# kegboard_rpt.net
KiCad netlist of a schematic drawn in EAGLE
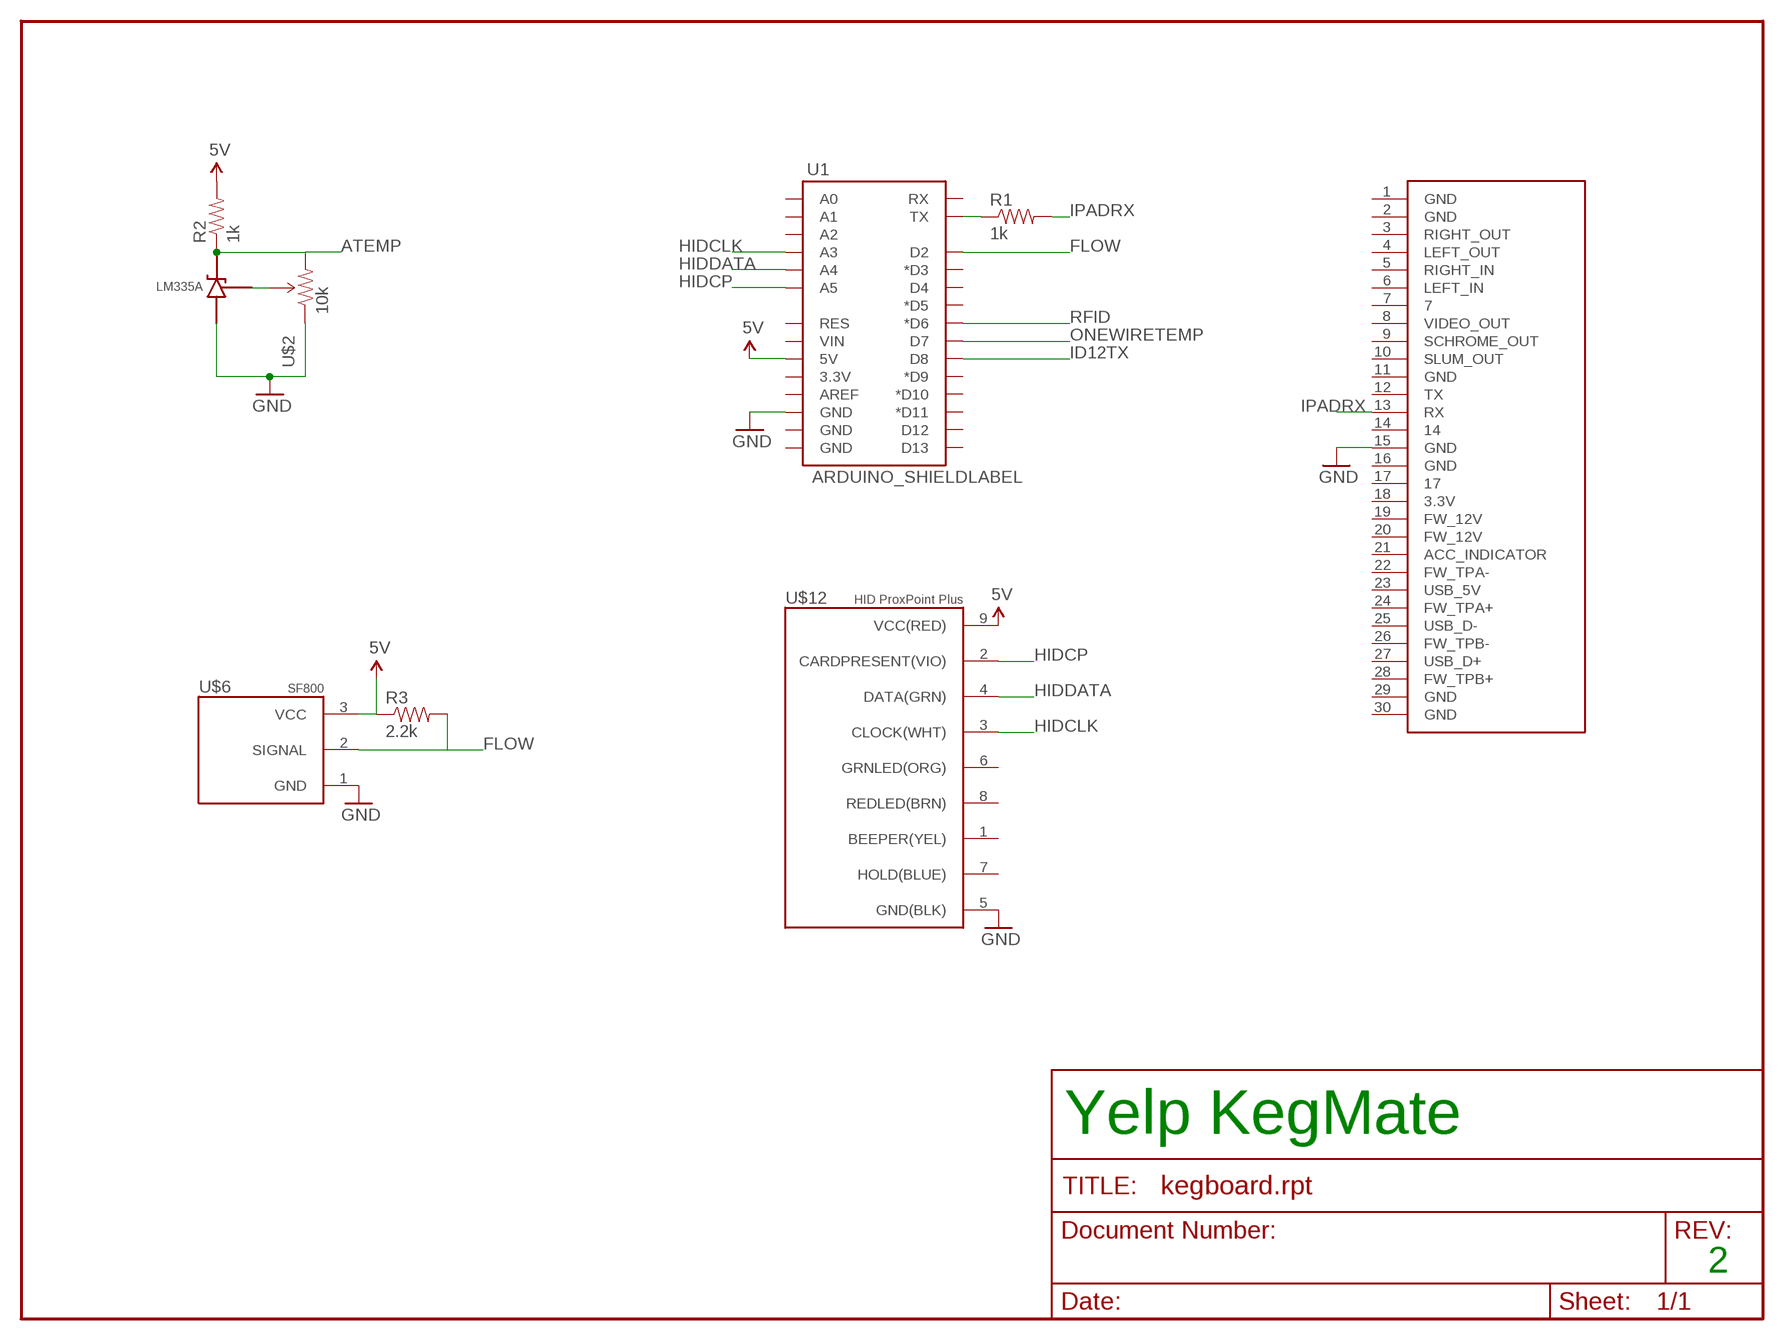
[diagram p0: schematic, sheet 1]

(export (version "E")
  (design (tool "Eeschema 10.0.6"))
  (components
    (comp (ref "R1")
      (value "1k")
      (footprint "eagle-import:AXIAL-0.3")
      (libsource (lib "eagle-import") (part "RESISTORPTH1"))
    )
    (comp (ref "R2")
      (value "1k")
      (footprint "eagle-import:AXIAL-0.3")
      (libsource (lib "eagle-import") (part "RESISTORPTH1"))
    )
    (comp (ref "R3")
      (value "2.2k")
      (footprint "eagle-import:AXIAL-0.3")
      (libsource (lib "eagle-import") (part "RESISTORPTH1"))
    )
    (comp (ref "U$1")
      (value "IPOD_CONNECTOR_MALE")
      (footprint "eagle-import:IPOD_MALE_CONNECTOR")
      (libsource (lib "eagle-import") (part "IPOD_CONNECTOR_MALE"))
    )
    (comp (ref "U$2")
      (value "10k")
      (footprint "eagle-import:3362U-2")
      (libsource (lib "eagle-import") (part "TRIMPOT"))
    )
    (comp (ref "U$6")
      (value "SF800")
      (footprint "eagle-import:1X03")
      (libsource (lib "eagle-import") (part "SF800"))
    )
    (comp (ref "U$11")
      (value "LM335A")
      (footprint "eagle-import:TO-92")
      (libsource (lib "eagle-import") (part "LM335A"))
    )
    (comp (ref "U$12")
      (value "HIDPROXPOINT")
      (footprint "eagle-import:2X5")
      (libsource (lib "eagle-import") (part "HIDPROXPOINT"))
    )
    (comp (ref "U1")
      (value "ARDUINO_SHIELDLABEL")
      (footprint "eagle-import:DUEMILANOVE_SHIELD")
      (libsource (lib "eagle-import") (part "ARDUINO_SHIELDLABEL"))
    )
  )
  (nets
    (net (code "1") (name "/ATEMP") (class "Default")
      (node (ref "R2") (pin "P$1") (pinfunction "1_P$1") (pintype "passive"))
      (node (ref "U$11") (pin "C1") (pinfunction "+_C1") (pintype "bidirectional"))
      (node (ref "U$2") (pin "3") (pinfunction "CW_3") (pintype "passive"))
    )
    (net (code "2") (name "/FLOW") (class "Default")
      (node (ref "R3") (pin "P$2") (pinfunction "2_P$2") (pintype "passive"))
      (node (ref "U$6") (pin "2") (pinfunction "SIGNAL_2") (pintype "bidirectional"))
      (node (ref "U1") (pin "D2") (pinfunction "D2_D2") (pintype "bidirectional"))
    )
    (net (code "3") (name "/HIDCLK") (class "Default")
      (node (ref "U$12") (pin "3") (pinfunction "CLOCK(WHT)_3") (pintype "bidirectional"))
      (node (ref "U1") (pin "A3") (pinfunction "A3_A3") (pintype "bidirectional"))
    )
    (net (code "4") (name "/HIDCP") (class "Default")
      (node (ref "U$12") (pin "2") (pinfunction "CARDPRESENT(VIO)_2") (pintype "bidirectional"))
      (node (ref "U1") (pin "A5") (pinfunction "A5_A5") (pintype "bidirectional"))
    )
    (net (code "5") (name "/HIDDATA") (class "Default")
      (node (ref "U$12") (pin "4") (pinfunction "DATA(GRN)_4") (pintype "bidirectional"))
      (node (ref "U1") (pin "A4") (pinfunction "A4_A4") (pintype "bidirectional"))
    )
    (net (code "6") (name "/ID12TX") (class "Default")
      (node (ref "U1") (pin "D8") (pinfunction "D8_D8") (pintype "bidirectional"))
    )
    (net (code "7") (name "/IPADRX") (class "Default")
      (node (ref "R1") (pin "P$2") (pinfunction "2_P$2") (pintype "passive"))
      (node (ref "U$1") (pin "13") (pinfunction "RX_13") (pintype "bidirectional"))
    )
    (net (code "8") (name "/ONEWIRETEMP") (class "Default")
      (node (ref "U1") (pin "D7") (pinfunction "D7_D7") (pintype "bidirectional"))
    )
    (net (code "9") (name "/RFID") (class "Default")
      (node (ref "U1") (pin "D6") (pinfunction "*D6_D6") (pintype "bidirectional"))
    )
    (net (code "10") (name "5V") (class "Default")
      (node (ref "R2") (pin "P$2") (pinfunction "2_P$2") (pintype "passive"))
      (node (ref "R3") (pin "P$1") (pinfunction "1_P$1") (pintype "passive"))
      (node (ref "U$12") (pin "9") (pinfunction "VCC(RED)_9") (pintype "bidirectional"))
      (node (ref "U$6") (pin "3") (pinfunction "VCC_3") (pintype "bidirectional"))
      (node (ref "U1") (pin "5V") (pinfunction "5V_5V") (pintype "bidirectional"))
    )
    (net (code "11") (name "GND") (class "Default")
      (node (ref "U$1") (pin "15") (pinfunction "GND_15") (pintype "bidirectional"))
      (node (ref "U$11") (pin "E1") (pinfunction "-_E1") (pintype "bidirectional"))
      (node (ref "U$12") (pin "5") (pinfunction "GND(BLK)_5") (pintype "bidirectional"))
      (node (ref "U$2") (pin "1") (pinfunction "CCW_1") (pintype "passive"))
      (node (ref "U$6") (pin "1") (pinfunction "GND_1") (pintype "bidirectional"))
      (node (ref "U1") (pin "GND@2") (pinfunction "GND_GND@2") (pintype "bidirectional"))
    )
    (net (code "12") (name "Net-(R1-1)") (class "Default")
      (node (ref "R1") (pin "P$1") (pinfunction "1_P$1") (pintype "passive"))
      (node (ref "U1") (pin "TX") (pinfunction "TX_TX") (pintype "bidirectional"))
    )
    (net (code "13") (name "Net-(U$11-ADJ)") (class "Default")
      (node (ref "U$11") (pin "B1") (pinfunction "ADJ_B1") (pintype "bidirectional"))
      (node (ref "U$2") (pin "2") (pinfunction "WIPER_2") (pintype "passive"))
    )
    (net (code "14") (name "unconnected-(U$1-3.3V-Pad18)") (class "Default")
      (node (ref "U$1") (pin "18") (pinfunction "3.3V_18") (pintype "bidirectional"))
    )
    (net (code "15") (name "unconnected-(U$1-ACC_INDICATOR-Pad21)") (class "Default")
      (node (ref "U$1") (pin "21") (pinfunction "ACC_INDICATOR_21") (pintype "bidirectional"))
    )
    (net (code "16") (name "unconnected-(U$1-FW_12V-Pad19)") (class "Default")
      (node (ref "U$1") (pin "19") (pinfunction "FW_12V_19") (pintype "bidirectional"))
    )
    (net (code "17") (name "unconnected-(U$1-FW_12V-Pad20)") (class "Default")
      (node (ref "U$1") (pin "20") (pinfunction "FW_12V_20") (pintype "bidirectional"))
    )
    (net (code "18") (name "unconnected-(U$1-FW_TPA+-Pad24)") (class "Default")
      (node (ref "U$1") (pin "24") (pinfunction "FW_TPA+_24") (pintype "bidirectional"))
    )
    (net (code "19") (name "unconnected-(U$1-FW_TPA--Pad22)") (class "Default")
      (node (ref "U$1") (pin "22") (pinfunction "FW_TPA-_22") (pintype "bidirectional"))
    )
    (net (code "20") (name "unconnected-(U$1-FW_TPB+-Pad28)") (class "Default")
      (node (ref "U$1") (pin "28") (pinfunction "FW_TPB+_28") (pintype "bidirectional"))
    )
    (net (code "21") (name "unconnected-(U$1-FW_TPB--Pad26)") (class "Default")
      (node (ref "U$1") (pin "26") (pinfunction "FW_TPB-_26") (pintype "bidirectional"))
    )
    (net (code "22") (name "unconnected-(U$1-GND-Pad1)") (class "Default")
      (node (ref "U$1") (pin "1") (pinfunction "GND_1") (pintype "bidirectional"))
    )
    (net (code "23") (name "unconnected-(U$1-GND-Pad2)") (class "Default")
      (node (ref "U$1") (pin "2") (pinfunction "GND_2") (pintype "bidirectional"))
    )
    (net (code "24") (name "unconnected-(U$1-GND-Pad11)") (class "Default")
      (node (ref "U$1") (pin "11") (pinfunction "GND_11") (pintype "bidirectional"))
    )
    (net (code "25") (name "unconnected-(U$1-GND-Pad16)") (class "Default")
      (node (ref "U$1") (pin "16") (pinfunction "GND_16") (pintype "bidirectional"))
    )
    (net (code "26") (name "unconnected-(U$1-GND-Pad29)") (class "Default")
      (node (ref "U$1") (pin "29") (pinfunction "GND_29") (pintype "bidirectional"))
    )
    (net (code "27") (name "unconnected-(U$1-GND-Pad30)") (class "Default")
      (node (ref "U$1") (pin "30") (pinfunction "GND_30") (pintype "bidirectional"))
    )
    (net (code "28") (name "unconnected-(U$1-LEFT_IN-Pad6)") (class "Default")
      (node (ref "U$1") (pin "6") (pinfunction "LEFT_IN_6") (pintype "bidirectional"))
    )
    (net (code "29") (name "unconnected-(U$1-LEFT_OUT-Pad4)") (class "Default")
      (node (ref "U$1") (pin "4") (pinfunction "LEFT_OUT_4") (pintype "bidirectional"))
    )
    (net (code "30") (name "unconnected-(U$1-Pad7)") (class "Default")
      (node (ref "U$1") (pin "7") (pinfunction "7_7") (pintype "bidirectional"))
    )
    (net (code "31") (name "unconnected-(U$1-Pad14)") (class "Default")
      (node (ref "U$1") (pin "14") (pinfunction "14_14") (pintype "bidirectional"))
    )
    (net (code "32") (name "unconnected-(U$1-Pad17)") (class "Default")
      (node (ref "U$1") (pin "17") (pinfunction "17_17") (pintype "bidirectional"))
    )
    (net (code "33") (name "unconnected-(U$1-RIGHT_IN-Pad5)") (class "Default")
      (node (ref "U$1") (pin "5") (pinfunction "RIGHT_IN_5") (pintype "bidirectional"))
    )
    (net (code "34") (name "unconnected-(U$1-RIGHT_OUT-Pad3)") (class "Default")
      (node (ref "U$1") (pin "3") (pinfunction "RIGHT_OUT_3") (pintype "bidirectional"))
    )
    (net (code "35") (name "unconnected-(U$1-SCHROME_OUT-Pad9)") (class "Default")
      (node (ref "U$1") (pin "9") (pinfunction "SCHROME_OUT_9") (pintype "bidirectional"))
    )
    (net (code "36") (name "unconnected-(U$1-SLUM_OUT-Pad10)") (class "Default")
      (node (ref "U$1") (pin "10") (pinfunction "SLUM_OUT_10") (pintype "bidirectional"))
    )
    (net (code "37") (name "unconnected-(U$1-TX-Pad12)") (class "Default")
      (node (ref "U$1") (pin "12") (pinfunction "TX_12") (pintype "bidirectional"))
    )
    (net (code "38") (name "unconnected-(U$1-USB_5V-Pad23)") (class "Default")
      (node (ref "U$1") (pin "23") (pinfunction "USB_5V_23") (pintype "bidirectional"))
    )
    (net (code "39") (name "unconnected-(U$1-USB_D+-Pad27)") (class "Default")
      (node (ref "U$1") (pin "27") (pinfunction "USB_D+_27") (pintype "bidirectional"))
    )
    (net (code "40") (name "unconnected-(U$1-USB_D--Pad25)") (class "Default")
      (node (ref "U$1") (pin "25") (pinfunction "USB_D-_25") (pintype "bidirectional"))
    )
    (net (code "41") (name "unconnected-(U$1-VIDEO_OUT-Pad8)") (class "Default")
      (node (ref "U$1") (pin "8") (pinfunction "VIDEO_OUT_8") (pintype "bidirectional"))
    )
    (net (code "42") (name "unconnected-(U$12-BEEPER(YEL)-Pad1)") (class "Default")
      (node (ref "U$12") (pin "1") (pinfunction "BEEPER(YEL)_1") (pintype "bidirectional"))
    )
    (net (code "43") (name "unconnected-(U$12-GRNLED(ORG)-Pad6)") (class "Default")
      (node (ref "U$12") (pin "6") (pinfunction "GRNLED(ORG)_6") (pintype "bidirectional"))
    )
    (net (code "44") (name "unconnected-(U$12-HOLD(BLUE)-Pad7)") (class "Default")
      (node (ref "U$12") (pin "7") (pinfunction "HOLD(BLUE)_7") (pintype "bidirectional"))
    )
    (net (code "45") (name "unconnected-(U$12-REDLED(BRN)-Pad8)") (class "Default")
      (node (ref "U$12") (pin "8") (pinfunction "REDLED(BRN)_8") (pintype "bidirectional"))
    )
    (net (code "46") (name "unconnected-(U1-*D3-PadD3)") (class "Default")
      (node (ref "U1") (pin "D3") (pinfunction "*D3_D3") (pintype "bidirectional"))
    )
    (net (code "47") (name "unconnected-(U1-*D5-PadD5)") (class "Default")
      (node (ref "U1") (pin "D5") (pinfunction "*D5_D5") (pintype "bidirectional"))
    )
    (net (code "48") (name "unconnected-(U1-*D9-PadD9)") (class "Default")
      (node (ref "U1") (pin "D9") (pinfunction "*D9_D9") (pintype "bidirectional"))
    )
    (net (code "49") (name "unconnected-(U1-*D10-PadD10)") (class "Default")
      (node (ref "U1") (pin "D10") (pinfunction "*D10_D10") (pintype "bidirectional"))
    )
    (net (code "50") (name "unconnected-(U1-*D11-PadD11)") (class "Default")
      (node (ref "U1") (pin "D11") (pinfunction "*D11_D11") (pintype "bidirectional"))
    )
    (net (code "51") (name "unconnected-(U1-GND-PadGND@0)") (class "Default")
      (node (ref "U1") (pin "GND@0") (pinfunction "GND_GND@0") (pintype "bidirectional"))
    )
    (net (code "52") (name "unconnected-(U1-GND-PadGND@1)") (class "Default")
      (node (ref "U1") (pin "GND@1") (pinfunction "GND_GND@1") (pintype "bidirectional"))
    )
    (net (code "53") (name "unconnected-(U1-Pad3.3V)") (class "Default")
      (node (ref "U1") (pin "3.3V") (pinfunction "3.3V_3.3V") (pintype "bidirectional"))
    )
    (net (code "54") (name "unconnected-(U1-PadA0)") (class "Default")
      (node (ref "U1") (pin "A0") (pinfunction "A0_A0") (pintype "bidirectional"))
    )
    (net (code "55") (name "unconnected-(U1-PadA1)") (class "Default")
      (node (ref "U1") (pin "A1") (pinfunction "A1_A1") (pintype "bidirectional"))
    )
    (net (code "56") (name "unconnected-(U1-PadA2)") (class "Default")
      (node (ref "U1") (pin "A2") (pinfunction "A2_A2") (pintype "bidirectional"))
    )
    (net (code "57") (name "unconnected-(U1-PadAREF)") (class "Default")
      (node (ref "U1") (pin "AREF") (pinfunction "AREF_AREF") (pintype "bidirectional"))
    )
    (net (code "58") (name "unconnected-(U1-PadD4)") (class "Default")
      (node (ref "U1") (pin "D4") (pinfunction "D4_D4") (pintype "bidirectional"))
    )
    (net (code "59") (name "unconnected-(U1-PadD12)") (class "Default")
      (node (ref "U1") (pin "D12") (pinfunction "D12_D12") (pintype "bidirectional"))
    )
    (net (code "60") (name "unconnected-(U1-PadD13)") (class "Default")
      (node (ref "U1") (pin "D13") (pinfunction "D13_D13") (pintype "bidirectional"))
    )
    (net (code "61") (name "unconnected-(U1-PadRES)") (class "Default")
      (node (ref "U1") (pin "RES") (pinfunction "RES_RES") (pintype "bidirectional"))
    )
    (net (code "62") (name "unconnected-(U1-PadRX)") (class "Default")
      (node (ref "U1") (pin "RX") (pinfunction "RX_RX") (pintype "bidirectional"))
    )
    (net (code "63") (name "unconnected-(U1-PadVIN)") (class "Default")
      (node (ref "U1") (pin "VIN") (pinfunction "VIN_VIN") (pintype "bidirectional"))
    )
  )
)
